# VectrexCard4.net
KiCad netlist of a schematic drawn in EAGLE
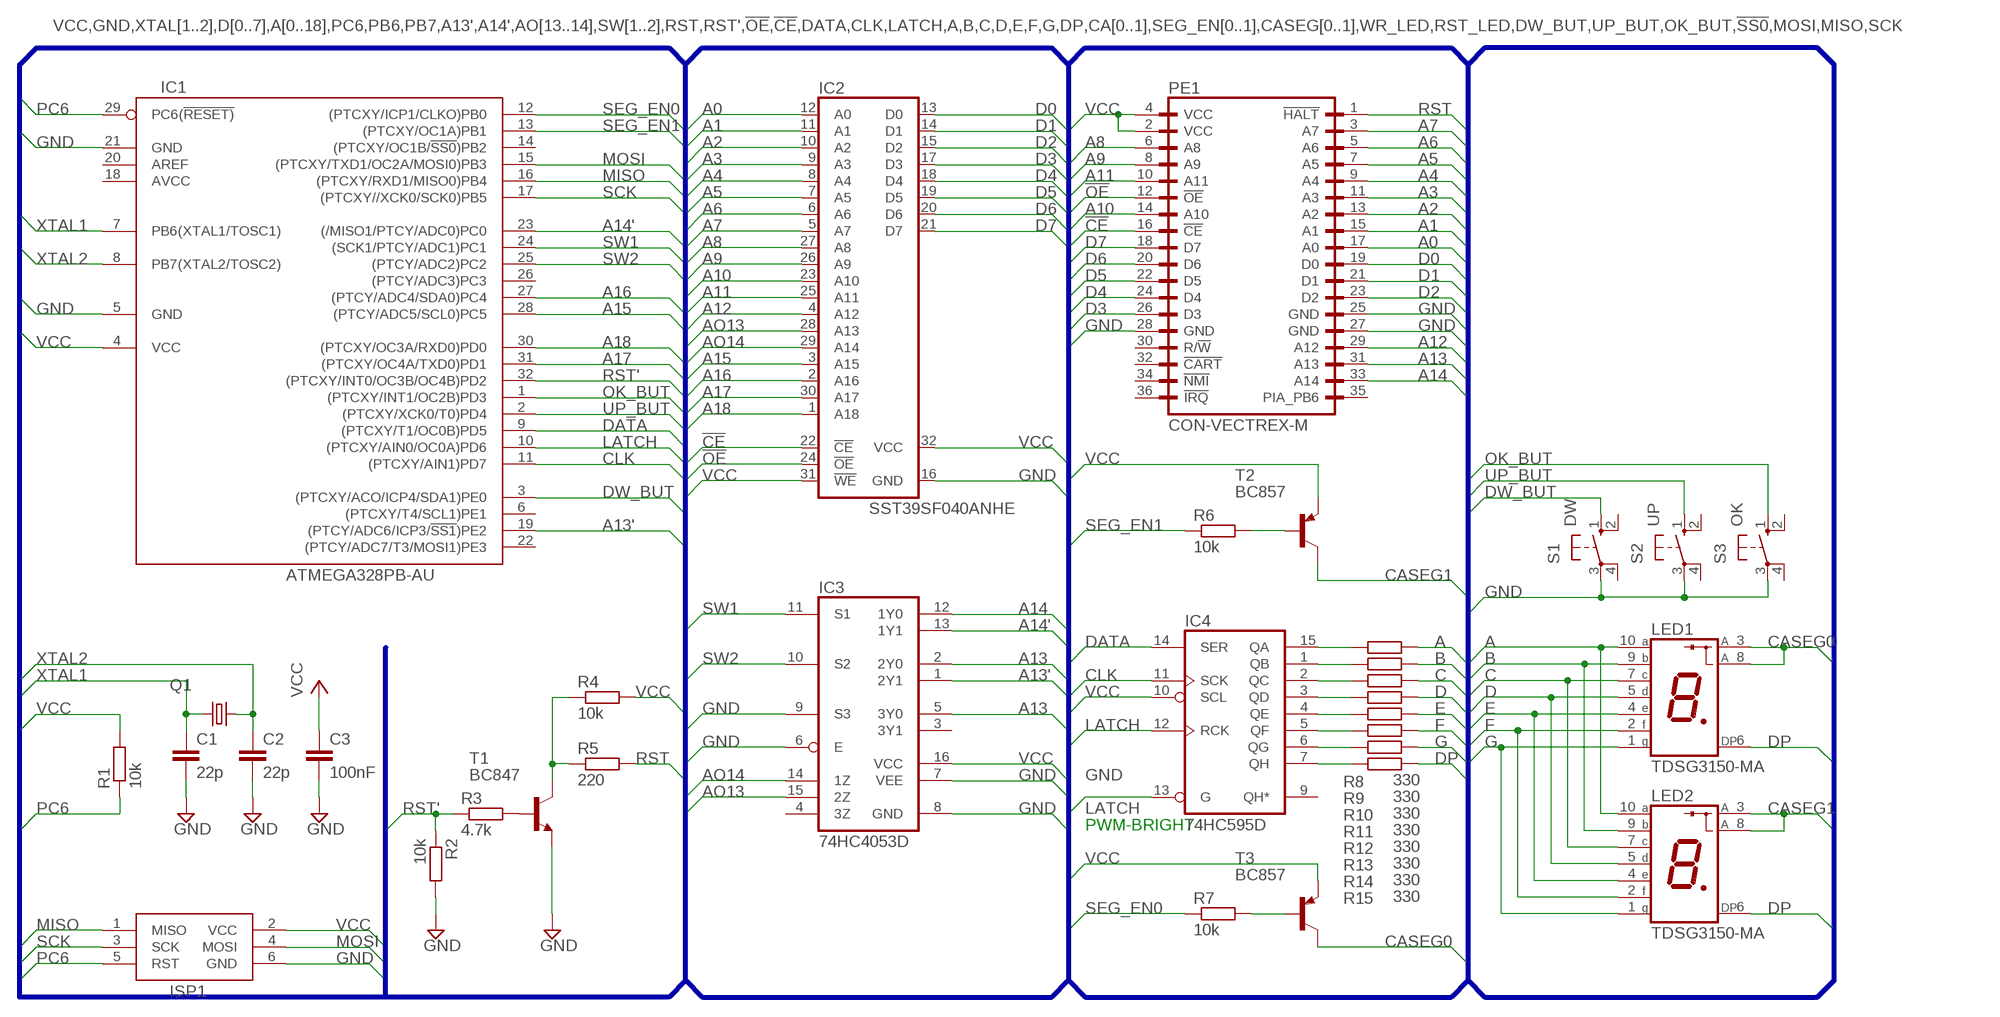
[diagram p0: schematic, sheet 1]

(export (version "E")
  (design (tool "Eeschema 10.0.6"))
  (components
    (comp (ref "C1")
      (value "22p")
      (footprint "eagle-import:C2012")
      (libsource (lib "eagle-import") (part "C-EUC2012"))
    )
    (comp (ref "C2")
      (value "22p")
      (footprint "eagle-import:C2012")
      (libsource (lib "eagle-import") (part "C-EUC2012"))
    )
    (comp (ref "C3")
      (value "100nF")
      (footprint "eagle-import:C050-025X075")
      (libsource (lib "eagle-import") (part "C-EU050-025X075"))
    )
    (comp (ref "IC1")
      (value "ATMEGA328PB-AU")
      (footprint "eagle-import:TQFP32-08")
      (libsource (lib "eagle-import") (part "ATMEGA328PB-AU"))
    )
    (comp (ref "IC2")
      (value "SST39SF040ANHE")
      (footprint "eagle-import:S32")
      (libsource (lib "eagle-import") (part "SST39SF040ANHE"))
    )
    (comp (ref "IC3")
      (value "74HC4053D")
      (footprint "eagle-import:SO16")
      (libsource (lib "eagle-import") (part "744053D"))
    )
    (comp (ref "IC4")
      (value "74HC595D")
      (footprint "eagle-import:SO16")
      (libsource (lib "eagle-import") (part "74595DHC"))
    )
    (comp (ref "ISP1")
      (value "AVRISP-6")
      (footprint "eagle-import:AVRISP")
      (libsource (lib "eagle-import") (part "AVRISP-6"))
    )
    (comp (ref "LED1")
      (value "TDSG3150-MA")
      (footprint "eagle-import:LA-401")
      (libsource (lib "eagle-import") (part "TDSG3150-MA"))
    )
    (comp (ref "LED2")
      (value "TDSG3150-MA")
      (footprint "eagle-import:LA-401")
      (libsource (lib "eagle-import") (part "TDSG3150-MA"))
    )
    (comp (ref "PE1")
      (value "CON-VECTREX-M")
      (footprint "eagle-import:PCB_VECTREX_CONNECTOR")
      (libsource (lib "eagle-import") (part "CON-VECTREX-M"))
    )
    (comp (ref "Q1")
      (value "8MHz")
      (footprint "eagle-import:HC49U-V")
      (libsource (lib "eagle-import") (part "CRYSTALHC49U-V"))
    )
    (comp (ref "R1")
      (value "10k")
      (footprint "eagle-import:0204_7")
      (libsource (lib "eagle-import") (part "R-EU_0204/7"))
    )
    (comp (ref "R2")
      (value "10k")
      (footprint "eagle-import:M2012")
      (libsource (lib "eagle-import") (part "R-EU_M2012"))
    )
    (comp (ref "R3")
      (value "4.7k")
      (footprint "eagle-import:M2012")
      (libsource (lib "eagle-import") (part "R-EU_M2012"))
    )
    (comp (ref "R4")
      (value "10k")
      (footprint "eagle-import:R2012")
      (libsource (lib "eagle-import") (part "R-EU_R2012"))
    )
    (comp (ref "R5")
      (value "220")
      (footprint "eagle-import:R2012")
      (libsource (lib "eagle-import") (part "R-EU_R2012"))
    )
    (comp (ref "R6")
      (value "10k")
      (footprint "eagle-import:M2012")
      (libsource (lib "eagle-import") (part "R-EU_M2012"))
    )
    (comp (ref "R7")
      (value "10k")
      (footprint "eagle-import:M2012")
      (libsource (lib "eagle-import") (part "R-EU_M2012"))
    )
    (comp (ref "R8")
      (value "330")
      (footprint "eagle-import:M2012")
      (libsource (lib "eagle-import") (part "R-EU_M2012"))
    )
    (comp (ref "R9")
      (value "330")
      (footprint "eagle-import:M2012")
      (libsource (lib "eagle-import") (part "R-EU_M2012"))
    )
    (comp (ref "R10")
      (value "330")
      (footprint "eagle-import:M2012")
      (libsource (lib "eagle-import") (part "R-EU_M2012"))
    )
    (comp (ref "R11")
      (value "330")
      (footprint "eagle-import:M2012")
      (libsource (lib "eagle-import") (part "R-EU_M2012"))
    )
    (comp (ref "R12")
      (value "330")
      (footprint "eagle-import:M2012")
      (libsource (lib "eagle-import") (part "R-EU_M2012"))
    )
    (comp (ref "R13")
      (value "330")
      (footprint "eagle-import:M2012")
      (libsource (lib "eagle-import") (part "R-EU_M2012"))
    )
    (comp (ref "R14")
      (value "330")
      (footprint "eagle-import:M2012")
      (libsource (lib "eagle-import") (part "R-EU_M2012"))
    )
    (comp (ref "R15")
      (value "330")
      (footprint "eagle-import:M2012")
      (libsource (lib "eagle-import") (part "R-EU_M2012"))
    )
    (comp (ref "S1")
      (value "DW")
      (footprint "eagle-import:B3F-10XX")
      (fields (field (name "MPN") "B3F-1000"))
      (libsource (lib "eagle-import") (part "10-XX"))
    )
    (comp (ref "S2")
      (value "UP")
      (footprint "eagle-import:B3F-10XX")
      (fields (field (name "MPN") "B3F-1000"))
      (libsource (lib "eagle-import") (part "10-XX"))
    )
    (comp (ref "S3")
      (value "OK")
      (footprint "eagle-import:B3F-10XX")
      (fields (field (name "MPN") "B3F-1000"))
      (libsource (lib "eagle-import") (part "10-XX"))
    )
    (comp (ref "T1")
      (value "BC847")
      (footprint "eagle-import:SOT23")
      (libsource (lib "eagle-import") (part "BC847"))
    )
    (comp (ref "T2")
      (value "BC857")
      (footprint "eagle-import:SOT23-BEC")
      (libsource (lib "eagle-import") (part "-PNP-SOT23-BECBC857A"))
    )
    (comp (ref "T3")
      (value "BC857")
      (footprint "eagle-import:SOT23-BEC")
      (libsource (lib "eagle-import") (part "-PNP-SOT23-BECBC857A"))
    )
  )
  (nets
    (net (code "6") (name "/A") (class "Default")
      (node (ref "LED1") (pin "10") (pinfunction "A_10") (pintype "passive"))
      (node (ref "LED2") (pin "10") (pinfunction "A_10") (pintype "passive"))
      (node (ref "R8") (pin "2") (pinfunction "2_2") (pintype "passive"))
    )
    (net (code "7") (name "/A0") (class "Default")
      (node (ref "IC2") (pin "12") (pinfunction "A0_12") (pintype "input"))
      (node (ref "PE1") (pin "17") (pinfunction "A0_17") (pintype "bidirectional"))
    )
    (net (code "8") (name "/A1") (class "Default")
      (node (ref "IC2") (pin "11") (pinfunction "A1_11") (pintype "input"))
      (node (ref "PE1") (pin "15") (pinfunction "A1_15") (pintype "bidirectional"))
    )
    (net (code "9") (name "/A2") (class "Default")
      (node (ref "IC2") (pin "10") (pinfunction "A2_10") (pintype "input"))
      (node (ref "PE1") (pin "13") (pinfunction "A2_13") (pintype "bidirectional"))
    )
    (net (code "10") (name "/A3") (class "Default")
      (node (ref "IC2") (pin "9") (pinfunction "A3_9") (pintype "input"))
      (node (ref "PE1") (pin "11") (pinfunction "A3_11") (pintype "bidirectional"))
    )
    (net (code "11") (name "/A4") (class "Default")
      (node (ref "IC2") (pin "8") (pinfunction "A4_8") (pintype "input"))
      (node (ref "PE1") (pin "9") (pinfunction "A4_9") (pintype "bidirectional"))
    )
    (net (code "12") (name "/A5") (class "Default")
      (node (ref "IC2") (pin "7") (pinfunction "A5_7") (pintype "input"))
      (node (ref "PE1") (pin "7") (pinfunction "A5_7") (pintype "bidirectional"))
    )
    (net (code "13") (name "/A6") (class "Default")
      (node (ref "IC2") (pin "6") (pinfunction "A6_6") (pintype "input"))
      (node (ref "PE1") (pin "5") (pinfunction "A6_5") (pintype "bidirectional"))
    )
    (net (code "14") (name "/A7") (class "Default")
      (node (ref "IC2") (pin "5") (pinfunction "A7_5") (pintype "input"))
      (node (ref "PE1") (pin "3") (pinfunction "A7_3") (pintype "bidirectional"))
    )
    (net (code "15") (name "/A8") (class "Default")
      (node (ref "IC2") (pin "27") (pinfunction "A8_27") (pintype "input"))
      (node (ref "PE1") (pin "6") (pinfunction "A8_6") (pintype "bidirectional"))
    )
    (net (code "16") (name "/A9") (class "Default")
      (node (ref "IC2") (pin "26") (pinfunction "A9_26") (pintype "input"))
      (node (ref "PE1") (pin "8") (pinfunction "A9_8") (pintype "bidirectional"))
    )
    (net (code "17") (name "/A10") (class "Default")
      (node (ref "IC2") (pin "23") (pinfunction "A10_23") (pintype "input"))
      (node (ref "PE1") (pin "14") (pinfunction "A10_14") (pintype "bidirectional"))
    )
    (net (code "18") (name "/A11") (class "Default")
      (node (ref "IC2") (pin "25") (pinfunction "A11_25") (pintype "input"))
      (node (ref "PE1") (pin "10") (pinfunction "A11_10") (pintype "bidirectional"))
    )
    (net (code "19") (name "/A12") (class "Default")
      (node (ref "IC2") (pin "4") (pinfunction "A12_4") (pintype "input"))
      (node (ref "PE1") (pin "29") (pinfunction "A12_29") (pintype "bidirectional"))
    )
    (net (code "20") (name "/A13") (class "Default")
      (node (ref "IC3") (pin "2") (pinfunction "2Y0_2") (pintype "bidirectional"))
      (node (ref "IC3") (pin "5") (pinfunction "3Y0_5") (pintype "bidirectional"))
      (node (ref "PE1") (pin "31") (pinfunction "A13_31") (pintype "bidirectional"))
    )
    (net (code "21") (name "/A13'") (class "Default")
      (node (ref "IC1") (pin "19") (pinfunction "(PTCY/ADC6/ICP3/~{SS1})PE2_19") (pintype "bidirectional"))
      (node (ref "IC3") (pin "1") (pinfunction "2Y1_1") (pintype "bidirectional"))
    )
    (net (code "22") (name "/A14") (class "Default")
      (node (ref "IC3") (pin "12") (pinfunction "1Y0_12") (pintype "bidirectional"))
      (node (ref "PE1") (pin "33") (pinfunction "A14_33") (pintype "bidirectional"))
    )
    (net (code "23") (name "/A14'") (class "Default")
      (node (ref "IC1") (pin "23") (pinfunction "(/MISO1/PTCY/ADC0)PC0_23") (pintype "bidirectional"))
      (node (ref "IC3") (pin "13") (pinfunction "1Y1_13") (pintype "bidirectional"))
    )
    (net (code "24") (name "/A15") (class "Default")
      (node (ref "IC1") (pin "28") (pinfunction "(PTCY/ADC5/SCL0)PC5_28") (pintype "bidirectional"))
      (node (ref "IC2") (pin "3") (pinfunction "A15_3") (pintype "input"))
    )
    (net (code "25") (name "/A16") (class "Default")
      (node (ref "IC1") (pin "27") (pinfunction "(PTCY/ADC4/SDA0)PC4_27") (pintype "bidirectional"))
      (node (ref "IC2") (pin "2") (pinfunction "A16_2") (pintype "input"))
    )
    (net (code "26") (name "/A17") (class "Default")
      (node (ref "IC1") (pin "31") (pinfunction "(PTCXY/OC4A/TXD0)PD1_31") (pintype "bidirectional"))
      (node (ref "IC2") (pin "30") (pinfunction "A17_30") (pintype "input"))
    )
    (net (code "27") (name "/A18") (class "Default")
      (node (ref "IC1") (pin "30") (pinfunction "(PTCXY/OC3A/RXD0)PD0_30") (pintype "bidirectional"))
      (node (ref "IC2") (pin "1") (pinfunction "A18_1") (pintype "input"))
    )
    (net (code "28") (name "/AO13") (class "Default")
      (node (ref "IC2") (pin "28") (pinfunction "A13_28") (pintype "input"))
      (node (ref "IC3") (pin "15") (pinfunction "2Z_15") (pintype "bidirectional"))
    )
    (net (code "29") (name "/AO14") (class "Default")
      (node (ref "IC2") (pin "29") (pinfunction "A14_29") (pintype "input"))
      (node (ref "IC3") (pin "14") (pinfunction "1Z_14") (pintype "bidirectional"))
    )
    (net (code "30") (name "/B") (class "Default")
      (node (ref "LED1") (pin "9") (pinfunction "B_9") (pintype "passive"))
      (node (ref "LED2") (pin "9") (pinfunction "B_9") (pintype "passive"))
      (node (ref "R9") (pin "2") (pinfunction "2_2") (pintype "passive"))
    )
    (net (code "31") (name "/C") (class "Default")
      (node (ref "LED1") (pin "7") (pinfunction "C_7") (pintype "passive"))
      (node (ref "LED2") (pin "7") (pinfunction "C_7") (pintype "passive"))
      (node (ref "R10") (pin "2") (pinfunction "2_2") (pintype "passive"))
    )
    (net (code "32") (name "/CASEG0") (class "Default")
      (node (ref "LED1") (pin "3") (pinfunction "A_3") (pintype "passive"))
      (node (ref "LED1") (pin "8") (pinfunction "A_8") (pintype "passive"))
      (node (ref "T3") (pin "C") (pinfunction "C_C") (pintype "passive"))
    )
    (net (code "33") (name "/CASEG1") (class "Default")
      (node (ref "LED2") (pin "3") (pinfunction "A_3") (pintype "passive"))
      (node (ref "LED2") (pin "8") (pinfunction "A_8") (pintype "passive"))
      (node (ref "T2") (pin "C") (pinfunction "C_C") (pintype "passive"))
    )
    (net (code "34") (name "/CLK") (class "Default")
      (node (ref "IC1") (pin "11") (pinfunction "(PTCXY/AIN1)PD7_11") (pintype "bidirectional"))
      (node (ref "IC4") (pin "11") (pinfunction "SCK_11") (pintype "input"))
    )
    (net (code "35") (name "/D") (class "Default")
      (node (ref "LED1") (pin "5") (pinfunction "D_5") (pintype "passive"))
      (node (ref "LED2") (pin "5") (pinfunction "D_5") (pintype "passive"))
      (node (ref "R11") (pin "2") (pinfunction "2_2") (pintype "passive"))
    )
    (net (code "36") (name "/D0") (class "Default")
      (node (ref "IC2") (pin "13") (pinfunction "D0_13") (pintype "bidirectional"))
      (node (ref "PE1") (pin "19") (pinfunction "D0_19") (pintype "output"))
    )
    (net (code "37") (name "/D1") (class "Default")
      (node (ref "IC2") (pin "14") (pinfunction "D1_14") (pintype "bidirectional"))
      (node (ref "PE1") (pin "21") (pinfunction "D1_21") (pintype "output"))
    )
    (net (code "38") (name "/D2") (class "Default")
      (node (ref "IC2") (pin "15") (pinfunction "D2_15") (pintype "bidirectional"))
      (node (ref "PE1") (pin "23") (pinfunction "D2_23") (pintype "output"))
    )
    (net (code "39") (name "/D3") (class "Default")
      (node (ref "IC2") (pin "17") (pinfunction "D3_17") (pintype "bidirectional"))
      (node (ref "PE1") (pin "26") (pinfunction "D3_26") (pintype "output"))
    )
    (net (code "40") (name "/D4") (class "Default")
      (node (ref "IC2") (pin "18") (pinfunction "D4_18") (pintype "bidirectional"))
      (node (ref "PE1") (pin "24") (pinfunction "D4_24") (pintype "output"))
    )
    (net (code "41") (name "/D5") (class "Default")
      (node (ref "IC2") (pin "19") (pinfunction "D5_19") (pintype "bidirectional"))
      (node (ref "PE1") (pin "22") (pinfunction "D5_22") (pintype "output"))
    )
    (net (code "42") (name "/D6") (class "Default")
      (node (ref "IC2") (pin "20") (pinfunction "D6_20") (pintype "bidirectional"))
      (node (ref "PE1") (pin "20") (pinfunction "D6_20") (pintype "output"))
    )
    (net (code "43") (name "/D7") (class "Default")
      (node (ref "IC2") (pin "21") (pinfunction "D7_21") (pintype "bidirectional"))
      (node (ref "PE1") (pin "18") (pinfunction "D7_18") (pintype "output"))
    )
    (net (code "44") (name "/DATA") (class "Default")
      (node (ref "IC1") (pin "9") (pinfunction "(PTCXY/T1/OC0B)PD5_9") (pintype "bidirectional"))
      (node (ref "IC4") (pin "14") (pinfunction "SER_14") (pintype "input"))
    )
    (net (code "45") (name "/DP") (class "Default")
      (node (ref "LED1") (pin "6") (pinfunction "DP_6") (pintype "passive"))
      (node (ref "LED2") (pin "6") (pinfunction "DP_6") (pintype "passive"))
      (node (ref "R15") (pin "2") (pinfunction "2_2") (pintype "passive"))
    )
    (net (code "46") (name "/DW_BUT") (class "Default")
      (node (ref "IC1") (pin "3") (pinfunction "(PTCXY/ACO/ICP4/SDA1)PE0_3") (pintype "bidirectional"))
      (node (ref "S1") (pin "1") (pinfunction "S_1") (pintype "passive"))
    )
    (net (code "47") (name "/E") (class "Default")
      (node (ref "LED1") (pin "4") (pinfunction "E_4") (pintype "passive"))
      (node (ref "LED2") (pin "4") (pinfunction "E_4") (pintype "passive"))
      (node (ref "R12") (pin "2") (pinfunction "2_2") (pintype "passive"))
    )
    (net (code "48") (name "/F") (class "Default")
      (node (ref "LED1") (pin "2") (pinfunction "F_2") (pintype "passive"))
      (node (ref "LED2") (pin "2") (pinfunction "F_2") (pintype "passive"))
      (node (ref "R13") (pin "2") (pinfunction "2_2") (pintype "passive"))
    )
    (net (code "49") (name "/G") (class "Default")
      (node (ref "LED1") (pin "1") (pinfunction "G_1") (pintype "passive"))
      (node (ref "LED2") (pin "1") (pinfunction "G_1") (pintype "passive"))
      (node (ref "R14") (pin "2") (pinfunction "2_2") (pintype "passive"))
    )
    (net (code "50") (name "/LATCH") (class "Default")
      (node (ref "IC1") (pin "10") (pinfunction "(PTCXY/AIN0/OC0A)PD6_10") (pintype "bidirectional"))
      (node (ref "IC4") (pin "12") (pinfunction "RCK_12") (pintype "input"))
    )
    (net (code "51") (name "/MISO") (class "Default")
      (node (ref "IC1") (pin "16") (pinfunction "(PTCXY/RXD1/MISO0)PB4_16") (pintype "bidirectional"))
      (node (ref "ISP1") (pin "1") (pinfunction "MISO_1") (pintype "input"))
    )
    (net (code "52") (name "/MOSI") (class "Default")
      (node (ref "IC1") (pin "15") (pinfunction "(PTCXY/TXD1/OC2A/MOSI0)PB3_15") (pintype "bidirectional"))
      (node (ref "ISP1") (pin "4") (pinfunction "MOSI_4") (pintype "output"))
    )
    (net (code "53") (name "/OK_BUT") (class "Default")
      (node (ref "IC1") (pin "1") (pinfunction "(PTCXY/INT1/OC2B)PD3_1") (pintype "bidirectional"))
      (node (ref "S3") (pin "1") (pinfunction "S_1") (pintype "passive"))
    )
    (net (code "54") (name "/PC6") (class "Default")
      (node (ref "IC1") (pin "29") (pinfunction "PC6(~{RESET})_29") (pintype "bidirectional"))
      (node (ref "ISP1") (pin "5") (pinfunction "RST_5") (pintype "output"))
      (node (ref "R1") (pin "1") (pinfunction "1_1") (pintype "passive"))
    )
    (net (code "55") (name "/RST") (class "Default")
      (node (ref "PE1") (pin "1") (pinfunction "~{HALT}_1") (pintype "bidirectional"))
      (node (ref "R5") (pin "2") (pinfunction "2_2") (pintype "passive"))
    )
    (net (code "56") (name "/RST'") (class "Default")
      (node (ref "IC1") (pin "32") (pinfunction "(PTCXY/INT0/OC3B/OC4B)PD2_32") (pintype "bidirectional"))
      (node (ref "R2") (pin "1") (pinfunction "1_1") (pintype "passive"))
      (node (ref "R3") (pin "1") (pinfunction "1_1") (pintype "passive"))
    )
    (net (code "57") (name "/SCK") (class "Default")
      (node (ref "IC1") (pin "17") (pinfunction "(PTCXY//XCK0/SCK0)PB5_17") (pintype "bidirectional"))
      (node (ref "ISP1") (pin "3") (pinfunction "SCK_3") (pintype "output"))
    )
    (net (code "58") (name "/SEG_EN0") (class "Default")
      (node (ref "IC1") (pin "12") (pinfunction "(PTCXY/ICP1/CLKO)PB0_12") (pintype "bidirectional"))
      (node (ref "R7") (pin "1") (pinfunction "1_1") (pintype "passive"))
    )
    (net (code "59") (name "/SEG_EN1") (class "Default")
      (node (ref "IC1") (pin "13") (pinfunction "(PTCXY/OC1A)PB1_13") (pintype "bidirectional"))
      (node (ref "R6") (pin "1") (pinfunction "1_1") (pintype "passive"))
    )
    (net (code "60") (name "/SW1") (class "Default")
      (node (ref "IC1") (pin "24") (pinfunction "(SCK1/PTCY/ADC1)PC1_24") (pintype "bidirectional"))
      (node (ref "IC3") (pin "11") (pinfunction "S1_11") (pintype "bidirectional"))
    )
    (net (code "61") (name "/SW2") (class "Default")
      (node (ref "IC1") (pin "25") (pinfunction "(PTCY/ADC2)PC2_25") (pintype "bidirectional"))
      (node (ref "IC3") (pin "10") (pinfunction "S2_10") (pintype "bidirectional"))
    )
    (net (code "62") (name "/UP_BUT") (class "Default")
      (node (ref "IC1") (pin "2") (pinfunction "(PTCXY/XCK0/T0)PD4_2") (pintype "bidirectional"))
      (node (ref "S2") (pin "1") (pinfunction "S_1") (pintype "passive"))
    )
    (net (code "63") (name "/XTAL1") (class "Default")
      (node (ref "C1") (pin "1") (pinfunction "1_1") (pintype "passive"))
      (node (ref "IC1") (pin "7") (pinfunction "PB6(XTAL1/TOSC1)_7") (pintype "bidirectional"))
      (node (ref "Q1") (pin "2") (pinfunction "2_2") (pintype "passive"))
    )
    (net (code "64") (name "/XTAL2") (class "Default")
      (node (ref "C2") (pin "1") (pinfunction "1_1") (pintype "passive"))
      (node (ref "IC1") (pin "8") (pinfunction "PB7(XTAL2/TOSC2)_8") (pintype "bidirectional"))
      (node (ref "Q1") (pin "1") (pinfunction "1_1") (pintype "passive"))
    )
    (net (code "66") (name "/~{CE}") (class "Default")
      (node (ref "IC2") (pin "22") (pinfunction "~{CE}_22") (pintype "input"))
      (node (ref "PE1") (pin "16") (pinfunction "~{CE}_16") (pintype "bidirectional"))
    )
    (net (code "67") (name "/~{OE}") (class "Default")
      (node (ref "IC2") (pin "24") (pinfunction "~{OE}_24") (pintype "input"))
      (node (ref "PE1") (pin "12") (pinfunction "~{OE}_12") (pintype "bidirectional"))
    )
    (net (code "68") (name "GND") (class "Default")
      (node (ref "C1") (pin "2") (pinfunction "2_2") (pintype "passive"))
      (node (ref "C2") (pin "2") (pinfunction "2_2") (pintype "passive"))
      (node (ref "C3") (pin "2") (pinfunction "2_2") (pintype "passive"))
      (node (ref "IC1") (pin "21") (pinfunction "GND_21") (pintype "power_in"))
      (node (ref "IC1") (pin "5") (pinfunction "GND_5") (pintype "power_in"))
      (node (ref "IC2") (pin "16") (pinfunction "GND_16") (pintype "power_in"))
      (node (ref "IC3") (pin "6") (pinfunction "E_6") (pintype "input"))
      (node (ref "IC3") (pin "7") (pinfunction "VEE_7") (pintype "power_in"))
      (node (ref "IC3") (pin "8") (pinfunction "GND_8") (pintype "power_in"))
      (node (ref "IC3") (pin "9") (pinfunction "S3_9") (pintype "bidirectional"))
      (node (ref "IC4") (pin "13") (pinfunction "G_13") (pintype "input"))
      (node (ref "ISP1") (pin "6") (pinfunction "GND_6") (pintype "power_in"))
      (node (ref "PE1") (pin "25") (pinfunction "GND_25") (pintype "power_in"))
      (node (ref "PE1") (pin "27") (pinfunction "GND_27") (pintype "passive"))
      (node (ref "PE1") (pin "28") (pinfunction "GND_28") (pintype "passive"))
      (node (ref "R2") (pin "2") (pinfunction "2_2") (pintype "passive"))
      (node (ref "S1") (pin "3") (pinfunction "P_3") (pintype "passive"))
      (node (ref "S2") (pin "3") (pinfunction "P_3") (pintype "passive"))
      (node (ref "S3") (pin "3") (pinfunction "P_3") (pintype "passive"))
      (node (ref "T1") (pin "2") (pinfunction "E_2") (pintype "passive"))
    )
    (net (code "69") (name "Net-(IC4A-QA)") (class "Default")
      (node (ref "IC4") (pin "15") (pinfunction "QA_15") (pintype "tri_state"))
      (node (ref "R8") (pin "1") (pinfunction "1_1") (pintype "passive"))
    )
    (net (code "70") (name "Net-(IC4A-QB)") (class "Default")
      (node (ref "IC4") (pin "1") (pinfunction "QB_1") (pintype "tri_state"))
      (node (ref "R9") (pin "1") (pinfunction "1_1") (pintype "passive"))
    )
    (net (code "71") (name "Net-(IC4A-QC)") (class "Default")
      (node (ref "IC4") (pin "2") (pinfunction "QC_2") (pintype "tri_state"))
      (node (ref "R10") (pin "1") (pinfunction "1_1") (pintype "passive"))
    )
    (net (code "72") (name "Net-(IC4A-QD)") (class "Default")
      (node (ref "IC4") (pin "3") (pinfunction "QD_3") (pintype "tri_state"))
      (node (ref "R11") (pin "1") (pinfunction "1_1") (pintype "passive"))
    )
    (net (code "73") (name "Net-(IC4A-QE)") (class "Default")
      (node (ref "IC4") (pin "4") (pinfunction "QE_4") (pintype "tri_state"))
      (node (ref "R12") (pin "1") (pinfunction "1_1") (pintype "passive"))
    )
    (net (code "74") (name "Net-(IC4A-QF)") (class "Default")
      (node (ref "IC4") (pin "5") (pinfunction "QF_5") (pintype "tri_state"))
      (node (ref "R13") (pin "1") (pinfunction "1_1") (pintype "passive"))
    )
    (net (code "75") (name "Net-(IC4A-QG)") (class "Default")
      (node (ref "IC4") (pin "6") (pinfunction "QG_6") (pintype "tri_state"))
      (node (ref "R14") (pin "1") (pinfunction "1_1") (pintype "passive"))
    )
    (net (code "76") (name "Net-(IC4A-QH)") (class "Default")
      (node (ref "IC4") (pin "7") (pinfunction "QH_7") (pintype "tri_state"))
      (node (ref "R15") (pin "1") (pinfunction "1_1") (pintype "passive"))
    )
    (net (code "77") (name "Net-(R6-Pad2)") (class "Default")
      (node (ref "R6") (pin "2") (pinfunction "2_2") (pintype "passive"))
      (node (ref "T2") (pin "B") (pinfunction "B_B") (pintype "passive"))
    )
    (net (code "78") (name "Net-(R7-Pad2)") (class "Default")
      (node (ref "R7") (pin "2") (pinfunction "2_2") (pintype "passive"))
      (node (ref "T3") (pin "B") (pinfunction "B_B") (pintype "passive"))
    )
    (net (code "79") (name "Net-(T1-B)") (class "Default")
      (node (ref "R3") (pin "2") (pinfunction "2_2") (pintype "passive"))
      (node (ref "T1") (pin "1") (pinfunction "B_1") (pintype "passive"))
    )
    (net (code "80") (name "Net-(T1-C)") (class "Default")
      (node (ref "R4") (pin "1") (pinfunction "1_1") (pintype "passive"))
      (node (ref "R5") (pin "1") (pinfunction "1_1") (pintype "passive"))
      (node (ref "T1") (pin "3") (pinfunction "C_3") (pintype "passive"))
    )
    (net (code "81") (name "VCC") (class "Default")
      (node (ref "C3") (pin "1") (pinfunction "1_1") (pintype "passive"))
      (node (ref "IC1") (pin "4") (pinfunction "VCC_4") (pintype "power_in"))
      (node (ref "IC2") (pin "31") (pinfunction "~{WE}_31") (pintype "input"))
      (node (ref "IC2") (pin "32") (pinfunction "VCC_32") (pintype "power_in"))
      (node (ref "IC3") (pin "16") (pinfunction "VCC_16") (pintype "power_in"))
      (node (ref "IC4") (pin "10") (pinfunction "SCL_10") (pintype "input"))
      (node (ref "ISP1") (pin "2") (pinfunction "VCC_2") (pintype "power_in"))
      (node (ref "PE1") (pin "2") (pinfunction "VCC_2") (pintype "passive"))
      (node (ref "PE1") (pin "4") (pinfunction "VCC_4") (pintype "power_in"))
      (node (ref "R1") (pin "2") (pinfunction "2_2") (pintype "passive"))
      (node (ref "R4") (pin "2") (pinfunction "2_2") (pintype "passive"))
      (node (ref "T2") (pin "E") (pinfunction "E_E") (pintype "passive"))
      (node (ref "T3") (pin "E") (pinfunction "E_E") (pintype "passive"))
    )
    (net (code "82") (name "unconnected-(IC1-(PTCXY{slash}OC1B{slash}~{SS0})PB2-Pad14)") (class "Default")
      (node (ref "IC1") (pin "14") (pinfunction "(PTCXY/OC1B/~{SS0})PB2_14") (pintype "bidirectional"))
    )
    (net (code "83") (name "unconnected-(IC1-(PTCXY{slash}T4{slash}SCL1)PE1-Pad6)") (class "Default")
      (node (ref "IC1") (pin "6") (pinfunction "(PTCXY/T4/SCL1)PE1_6") (pintype "bidirectional"))
    )
    (net (code "84") (name "unconnected-(IC1-(PTCY{slash}ADC3)PC3-Pad26)") (class "Default")
      (node (ref "IC1") (pin "26") (pinfunction "(PTCY/ADC3)PC3_26") (pintype "bidirectional"))
    )
    (net (code "85") (name "unconnected-(IC1-(PTCY{slash}ADC7{slash}T3{slash}MOSI1)PE3-Pad22)") (class "Default")
      (node (ref "IC1") (pin "22") (pinfunction "(PTCY/ADC7/T3/MOSI1)PE3_22") (pintype "bidirectional"))
    )
    (net (code "86") (name "unconnected-(IC1-AREF-Pad20)") (class "Default")
      (node (ref "IC1") (pin "20") (pinfunction "AREF_20") (pintype "passive"))
    )
    (net (code "87") (name "unconnected-(IC1-AVCC-Pad18)") (class "Default")
      (node (ref "IC1") (pin "18") (pinfunction "AVCC_18") (pintype "passive"))
    )
    (net (code "88") (name "unconnected-(IC3-3Y1-Pad3)") (class "Default")
      (node (ref "IC3") (pin "3") (pinfunction "3Y1_3") (pintype "bidirectional"))
    )
    (net (code "89") (name "unconnected-(IC3-3Z-Pad4)") (class "Default")
      (node (ref "IC3") (pin "4") (pinfunction "3Z_4") (pintype "bidirectional"))
    )
    (net (code "90") (name "unconnected-(IC4A-QH*-Pad9)") (class "Default")
      (node (ref "IC4") (pin "9") (pinfunction "QH*_9") (pintype "tri_state"))
    )
    (net (code "91") (name "unconnected-(PE1-PIA_PB6-Pad35)") (class "Default")
      (node (ref "PE1") (pin "35") (pinfunction "PIA_PB6_35") (pintype "bidirectional"))
    )
    (net (code "92") (name "unconnected-(PE1-R{slash}~{W}-Pad30)") (class "Default")
      (node (ref "PE1") (pin "30") (pinfunction "R/~{W}_30") (pintype "no_connect"))
    )
    (net (code "93") (name "unconnected-(PE1-~{CART}-Pad32)") (class "Default")
      (node (ref "PE1") (pin "32") (pinfunction "~{CART}_32") (pintype "bidirectional"))
    )
    (net (code "94") (name "unconnected-(PE1-~{IRQ}-Pad36)") (class "Default")
      (node (ref "PE1") (pin "36") (pinfunction "~{IRQ}_36") (pintype "no_connect"))
    )
    (net (code "95") (name "unconnected-(PE1-~{NMI}-Pad34)") (class "Default")
      (node (ref "PE1") (pin "34") (pinfunction "~{NMI}_34") (pintype "no_connect"))
    )
    (net (code "96") (name "unconnected-(S1-P1-Pad4)") (class "Default")
      (node (ref "S1") (pin "4") (pinfunction "P1_4") (pintype "passive"))
    )
    (net (code "97") (name "unconnected-(S1-S1-Pad2)") (class "Default")
      (node (ref "S1") (pin "2") (pinfunction "S1_2") (pintype "passive"))
    )
    (net (code "98") (name "unconnected-(S2-P1-Pad4)") (class "Default")
      (node (ref "S2") (pin "4") (pinfunction "P1_4") (pintype "passive"))
    )
    (net (code "99") (name "unconnected-(S2-S1-Pad2)") (class "Default")
      (node (ref "S2") (pin "2") (pinfunction "S1_2") (pintype "passive"))
    )
    (net (code "100") (name "unconnected-(S3-P1-Pad4)") (class "Default")
      (node (ref "S3") (pin "4") (pinfunction "P1_4") (pintype "passive"))
    )
    (net (code "101") (name "unconnected-(S3-S1-Pad2)") (class "Default")
      (node (ref "S3") (pin "2") (pinfunction "S1_2") (pintype "passive"))
    )
  )
)
